# Input_Subsystem.net
KiCad netlist of a schematic drawn in Altium Designer
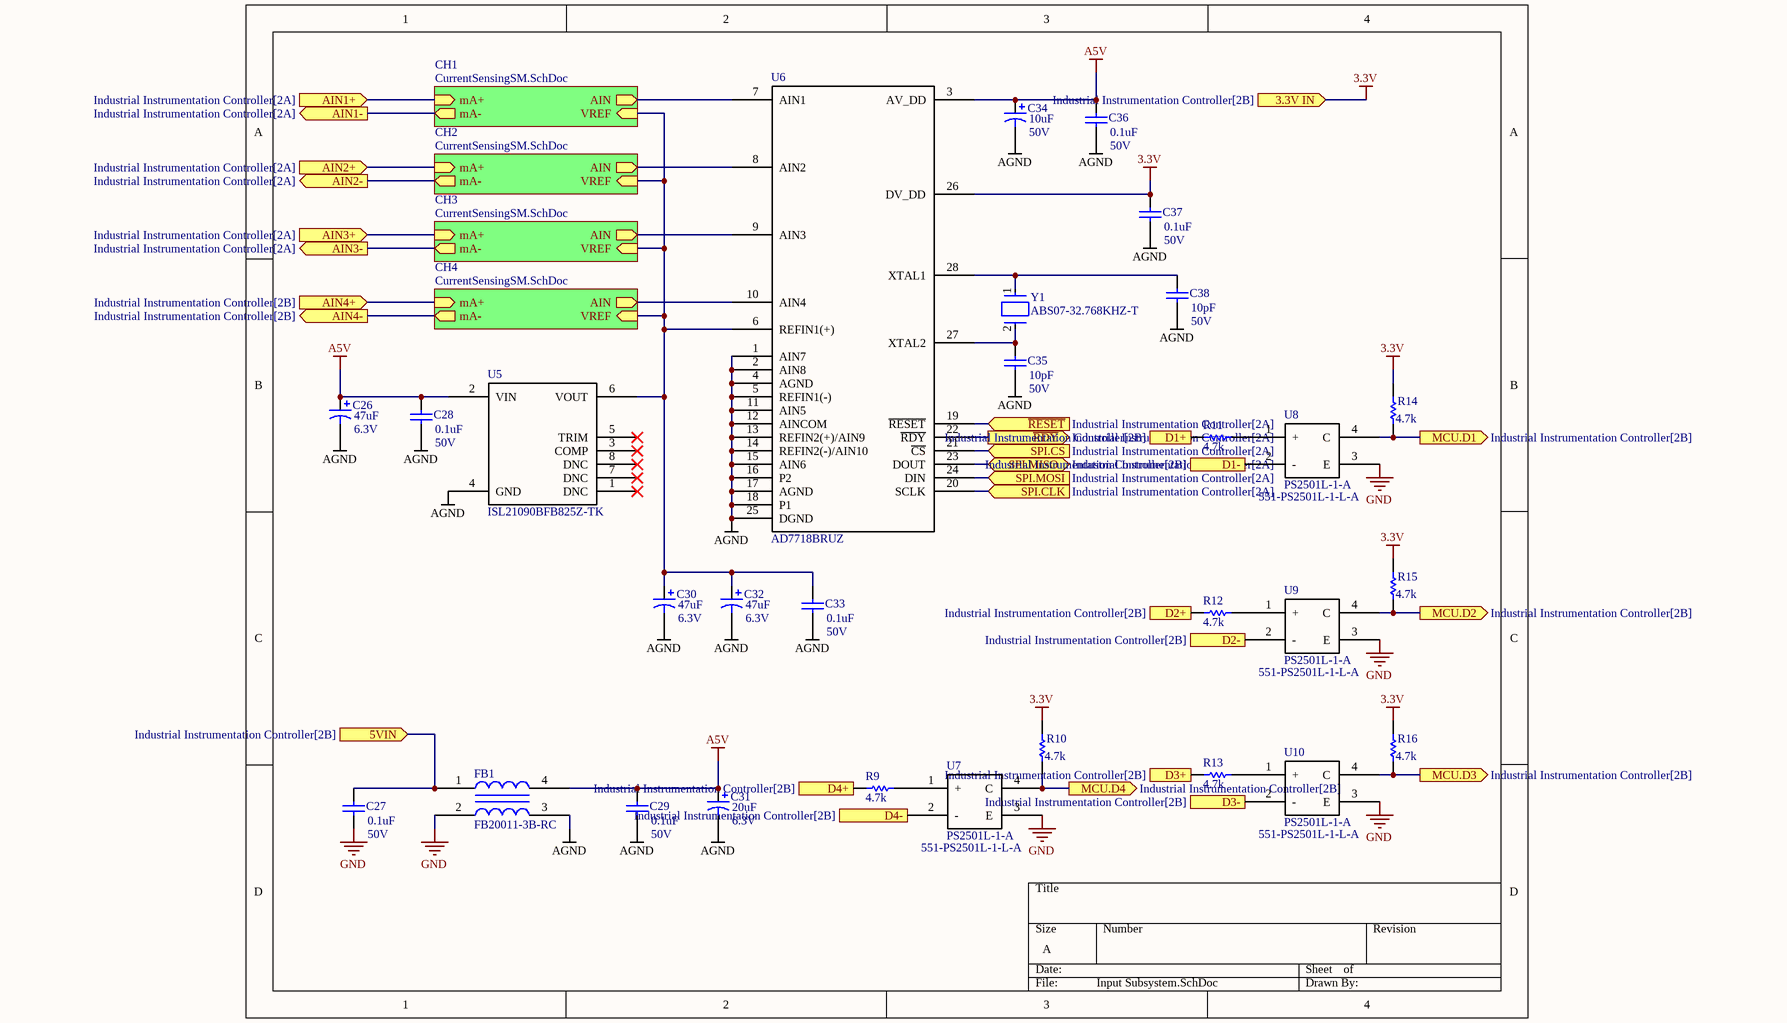
[diagram p0: Input Subsystem.SchDoc]

(export (version "E")
  (design (tool "Eeschema 10.0.6"))
  (components
    (comp (ref "C26")
      (value "47uF")
      (footprint "RB7.6-15")
      (description "Polarized Capacitor (Radial)")
      (fields
        (field (name "VOLTAGE RATING") "6.3V")
        (field (name "Comment") "Cap Pol1")
        (field (name "PUBLISHER") "Altium Limited")
      )
      (libsource (lib "Miscellaneous Devices") (part "Cap Pol1"))
    )
    (comp (ref "C27")
      (value "0.1uF")
      (footprint "RAD-0.3")
      (description "Capacitor")
      (fields
        (field (name "VOLTAGE RATING") "50V")
        (field (name "Comment") "Cap")
        (field (name "PUBLISHER") "Altium Limited")
      )
      (libsource (lib "Miscellaneous Devices") (part "Cap"))
    )
    (comp (ref "C28")
      (value "0.1uF")
      (footprint "RAD-0.3")
      (description "Capacitor")
      (fields
        (field (name "VOLTAGE RATING") "50V")
        (field (name "Comment") "Cap")
        (field (name "PUBLISHER") "Altium Limited")
      )
      (libsource (lib "Miscellaneous Devices") (part "Cap"))
    )
    (comp (ref "C29")
      (value "0.1uF")
      (footprint "RAD-0.3")
      (description "Capacitor")
      (fields
        (field (name "VOLTAGE RATING") "50V")
        (field (name "Comment") "Cap")
        (field (name "PUBLISHER") "Altium Limited")
      )
      (libsource (lib "Miscellaneous Devices") (part "Cap"))
    )
    (comp (ref "C30")
      (value "47uF")
      (footprint "RB7.6-15")
      (description "Polarized Capacitor (Radial)")
      (fields
        (field (name "VOLTAGE RATING") "6.3V")
        (field (name "Comment") "Cap Pol1")
        (field (name "PUBLISHER") "Altium Limited")
      )
      (libsource (lib "Miscellaneous Devices") (part "Cap Pol1"))
    )
    (comp (ref "C31")
      (value "20uF")
      (footprint "RB7.6-15")
      (description "Polarized Capacitor (Radial)")
      (fields
        (field (name "VOLTAGE RATING") "6.3V")
        (field (name "Comment") "Cap Pol1")
        (field (name "PUBLISHER") "Altium Limited")
      )
      (libsource (lib "Miscellaneous Devices") (part "Cap Pol1"))
    )
    (comp (ref "C32")
      (value "47uF")
      (footprint "RB7.6-15")
      (description "Polarized Capacitor (Radial)")
      (fields
        (field (name "VOLTAGE RATING") "6.3V")
        (field (name "Comment") "Cap Pol1")
        (field (name "PUBLISHER") "Altium Limited")
      )
      (libsource (lib "Miscellaneous Devices") (part "Cap Pol1"))
    )
    (comp (ref "C33")
      (value "0.1uF")
      (footprint "RAD-0.3")
      (description "Capacitor")
      (fields
        (field (name "VOLTAGE RATING") "50V")
        (field (name "Comment") "Cap")
        (field (name "PUBLISHER") "Altium Limited")
      )
      (libsource (lib "Miscellaneous Devices") (part "Cap"))
    )
    (comp (ref "C34")
      (value "10uF")
      (footprint "RB7.6-15")
      (description "Polarized Capacitor (Radial)")
      (fields
        (field (name "VOLTAGE RATING") "50V")
        (field (name "Comment") "Cap Pol1")
        (field (name "PUBLISHER") "Altium Limited")
      )
      (libsource (lib "Miscellaneous Devices") (part "Cap Pol1"))
    )
    (comp (ref "C35")
      (value "10pF")
      (footprint "RAD-0.3")
      (description "Capacitor")
      (fields
        (field (name "VOLTAGE RATING") "50V")
        (field (name "Comment") "Cap")
        (field (name "PUBLISHER") "Altium Limited")
      )
      (libsource (lib "Miscellaneous Devices") (part "Cap"))
    )
    (comp (ref "C36")
      (value "0.1uF")
      (footprint "RAD-0.3")
      (description "Capacitor")
      (fields
        (field (name "VOLTAGE RATING") "50V")
        (field (name "Comment") "Cap")
        (field (name "PUBLISHER") "Altium Limited")
      )
      (libsource (lib "Miscellaneous Devices") (part "Cap"))
    )
    (comp (ref "C37")
      (value "0.1uF")
      (footprint "RAD-0.3")
      (description "Capacitor")
      (fields
        (field (name "VOLTAGE RATING") "50V")
        (field (name "Comment") "Cap")
        (field (name "PUBLISHER") "Altium Limited")
      )
      (libsource (lib "Miscellaneous Devices") (part "Cap"))
    )
    (comp (ref "C38")
      (value "10pF")
      (footprint "RAD-0.3")
      (description "Capacitor")
      (fields
        (field (name "VOLTAGE RATING") "50V")
        (field (name "Comment") "Cap")
        (field (name "PUBLISHER") "Altium Limited")
      )
      (libsource (lib "Miscellaneous Devices") (part "Cap"))
    )
    (comp (ref "FB1")
      (value "FB20011-3B-RC")
      (footprint "FB20011")
      (libsource (lib "Parts") (part "FB20011"))
    )
    (comp (ref "R9")
      (value "4.7k")
      (footprint "AXIAL-0.3")
      (description "Resistor")
      (fields (field (name "Comment") "Res1") (field (name "PUBLISHER") "Altium Limited"))
      (libsource (lib "Miscellaneous Devices") (part "Res1"))
    )
    (comp (ref "R10")
      (value "4.7k")
      (footprint "AXIAL-0.3")
      (description "Resistor")
      (fields (field (name "Comment") "Res1") (field (name "PUBLISHER") "Altium Limited"))
      (libsource (lib "Miscellaneous Devices") (part "Res1"))
    )
    (comp (ref "R11")
      (value "4.7k")
      (footprint "AXIAL-0.3")
      (description "Resistor")
      (fields (field (name "Comment") "Res1") (field (name "PUBLISHER") "Altium Limited"))
      (libsource (lib "Miscellaneous Devices") (part "Res1"))
    )
    (comp (ref "R12")
      (value "4.7k")
      (footprint "AXIAL-0.3")
      (description "Resistor")
      (fields (field (name "Comment") "Res1") (field (name "PUBLISHER") "Altium Limited"))
      (libsource (lib "Miscellaneous Devices") (part "Res1"))
    )
    (comp (ref "R13")
      (value "4.7k")
      (footprint "AXIAL-0.3")
      (description "Resistor")
      (fields (field (name "Comment") "Res1") (field (name "PUBLISHER") "Altium Limited"))
      (libsource (lib "Miscellaneous Devices") (part "Res1"))
    )
    (comp (ref "R14")
      (value "4.7k")
      (footprint "AXIAL-0.3")
      (description "Resistor")
      (fields (field (name "Comment") "Res1") (field (name "PUBLISHER") "Altium Limited"))
      (libsource (lib "Miscellaneous Devices") (part "Res1"))
    )
    (comp (ref "R15")
      (value "4.7k")
      (footprint "AXIAL-0.3")
      (description "Resistor")
      (fields (field (name "Comment") "Res1") (field (name "PUBLISHER") "Altium Limited"))
      (libsource (lib "Miscellaneous Devices") (part "Res1"))
    )
    (comp (ref "R16")
      (value "4.7k")
      (footprint "AXIAL-0.3")
      (description "Resistor")
      (fields (field (name "Comment") "Res1") (field (name "PUBLISHER") "Altium Limited"))
      (libsource (lib "Miscellaneous Devices") (part "Res1"))
    )
    (comp (ref "U5")
      (value "ISL21090BFB825Z-TK")
      (footprint "ISL21090BFB825Z-TK")
      (libsource (lib "Parts") (part "ISL21090BFB825Z-TK"))
    )
    (comp (ref "U6")
      (value "AD7718BRUZ")
      (footprint "AD7718BRUZ")
      (libsource (lib "Parts") (part "AD7718BRUZ"))
    )
    (comp (ref "U7")
      (value "PS2501L-1-A")
      (footprint "PS2501L-1-A")
      (description "Optocoupler DC-IN 1-CH Transistor DC-OUT 4-Pin PDIP SMD Magazine")
      (fields
        (field (name "SUPPLIER PART NUMBER 1") "551-PS2501L-1-L-A")
        (field (name "MANUFACTURER") "CEL")
        (field (name "MANUFACTURER PART NUMBER") "PS2501L-1-L-A")
      )
      (libsource (lib "Parts") (part "PS2501L-1-A"))
    )
    (comp (ref "U8")
      (value "PS2501L-1-A")
      (footprint "PS2501L-1-A")
      (description "Optocoupler DC-IN 1-CH Transistor DC-OUT 4-Pin PDIP SMD Magazine")
      (fields
        (field (name "SUPPLIER PART NUMBER 1") "551-PS2501L-1-L-A")
        (field (name "MANUFACTURER") "CEL")
        (field (name "MANUFACTURER PART NUMBER") "PS2501L-1-L-A")
      )
      (libsource (lib "Parts") (part "PS2501L-1-A"))
    )
    (comp (ref "U9")
      (value "PS2501L-1-A")
      (footprint "PS2501L-1-A")
      (description "Optocoupler DC-IN 1-CH Transistor DC-OUT 4-Pin PDIP SMD Magazine")
      (fields
        (field (name "SUPPLIER PART NUMBER 1") "551-PS2501L-1-L-A")
        (field (name "MANUFACTURER") "CEL")
        (field (name "MANUFACTURER PART NUMBER") "PS2501L-1-L-A")
      )
      (libsource (lib "Parts") (part "PS2501L-1-A"))
    )
    (comp (ref "U10")
      (value "PS2501L-1-A")
      (footprint "PS2501L-1-A")
      (description "Optocoupler DC-IN 1-CH Transistor DC-OUT 4-Pin PDIP SMD Magazine")
      (fields
        (field (name "SUPPLIER PART NUMBER 1") "551-PS2501L-1-L-A")
        (field (name "MANUFACTURER") "CEL")
        (field (name "MANUFACTURER PART NUMBER") "PS2501L-1-L-A")
      )
      (libsource (lib "Parts") (part "PS2501L-1-A"))
    )
    (comp (ref "Y1")
      (value "ABS07-32.768KHZ-T")
      (footprint "FP-ABS07-MFG")
      (description "Crystal 32.768kHz ±20ppm (Tol) 12.5pF FUND 70kΩ 2-Pin CSMD T/R")
      (fields (field (name "TOLERANCE") "20ppm"))
      (libsource (lib "Altium Content Vault") (part "c23a69dc6c9e2f18f2079038eb95dd1"))
    )
  )
  (nets
    (net (code "1") (name "/5VIN") (class "Default")
      (node (ref "C27") (pin "2") (pinfunction "2_2") (pintype "passive"))
      (node (ref "FB1") (pin "1") (pinfunction "5V_1") (pintype "passive"))
    )
    (net (code "2") (name "/AIN") (class "Default")
      (node (ref "U6") (pin "9") (pinfunction "AIN3_9") (pintype "passive"))
    )
    (net (code "11") (name "/AIN_1") (class "Default")
      (node (ref "U6") (pin "10") (pinfunction "AIN4_10") (pintype "passive"))
    )
    (net (code "12") (name "/AIN_2") (class "Default")
      (node (ref "U6") (pin "7") (pinfunction "AIN1_7") (pintype "passive"))
    )
    (net (code "13") (name "/AIN_3") (class "Default")
      (node (ref "U6") (pin "8") (pinfunction "AIN2_8") (pintype "passive"))
    )
    (net (code "14") (name "/D1+") (class "Default")
      (node (ref "R11") (pin "2") (pinfunction "2_2") (pintype "passive"))
    )
    (net (code "15") (name "/D1-") (class "Default")
      (node (ref "U8") (pin "2") (pinfunction "-_2") (pintype "passive"))
    )
    (net (code "16") (name "/D2+") (class "Default")
      (node (ref "R12") (pin "2") (pinfunction "2_2") (pintype "passive"))
    )
    (net (code "17") (name "/D2-") (class "Default")
      (node (ref "U9") (pin "2") (pinfunction "-_2") (pintype "passive"))
    )
    (net (code "18") (name "/D3+") (class "Default")
      (node (ref "R13") (pin "2") (pinfunction "2_2") (pintype "passive"))
    )
    (net (code "19") (name "/D3-") (class "Default")
      (node (ref "U10") (pin "2") (pinfunction "-_2") (pintype "passive"))
    )
    (net (code "20") (name "/D4+") (class "Default")
      (node (ref "R9") (pin "2") (pinfunction "2_2") (pintype "passive"))
    )
    (net (code "21") (name "/D4-") (class "Default")
      (node (ref "U7") (pin "2") (pinfunction "-_2") (pintype "passive"))
    )
    (net (code "22") (name "/MCU.D1") (class "Default")
      (node (ref "R14") (pin "1") (pinfunction "1_1") (pintype "passive"))
      (node (ref "U8") (pin "4") (pinfunction "C_4") (pintype "passive"))
    )
    (net (code "23") (name "/MCU.D2") (class "Default")
      (node (ref "R15") (pin "1") (pinfunction "1_1") (pintype "passive"))
      (node (ref "U9") (pin "4") (pinfunction "C_4") (pintype "passive"))
    )
    (net (code "24") (name "/MCU.D3") (class "Default")
      (node (ref "R16") (pin "1") (pinfunction "1_1") (pintype "passive"))
      (node (ref "U10") (pin "4") (pinfunction "C_4") (pintype "passive"))
    )
    (net (code "25") (name "/MCU.D4") (class "Default")
      (node (ref "R10") (pin "1") (pinfunction "1_1") (pintype "passive"))
      (node (ref "U7") (pin "4") (pinfunction "C_4") (pintype "passive"))
    )
    (net (code "26") (name "/SPI.CLK") (class "Default")
      (node (ref "U6") (pin "20") (pinfunction "SCLK_20") (pintype "passive"))
    )
    (net (code "27") (name "/SPI.CS") (class "Default")
      (node (ref "U6") (pin "21") (pinfunction "~{CS}_21") (pintype "passive"))
    )
    (net (code "28") (name "/SPI.MISO") (class "Default")
      (node (ref "U6") (pin "23") (pinfunction "DOUT_23") (pintype "passive"))
    )
    (net (code "29") (name "/SPI.MOSI") (class "Default")
      (node (ref "U6") (pin "24") (pinfunction "DIN_24") (pintype "passive"))
    )
    (net (code "30") (name "/VREF") (class "Default")
      (node (ref "C30") (pin "1") (pinfunction "1_1") (pintype "passive"))
      (node (ref "C32") (pin "1") (pinfunction "1_1") (pintype "passive"))
      (node (ref "C33") (pin "2") (pinfunction "2_2") (pintype "passive"))
      (node (ref "U5") (pin "6") (pinfunction "VOUT_6") (pintype "passive"))
      (node (ref "U6") (pin "6") (pinfunction "REFIN1(+)_6") (pintype "passive"))
    )
    (net (code "31") (name "/~{RDY}") (class "Default")
      (node (ref "U6") (pin "22") (pinfunction "~{RDY}_22") (pintype "passive"))
    )
    (net (code "32") (name "/~{RESET}") (class "Default")
      (node (ref "U6") (pin "19") (pinfunction "~{RESET}_19") (pintype "passive"))
    )
    (net (code "33") (name "3.3V") (class "Default")
      (node (ref "C37") (pin "2") (pinfunction "2_2") (pintype "passive"))
      (node (ref "R10") (pin "2") (pinfunction "2_2") (pintype "passive"))
      (node (ref "R14") (pin "2") (pinfunction "2_2") (pintype "passive"))
      (node (ref "R15") (pin "2") (pinfunction "2_2") (pintype "passive"))
      (node (ref "R16") (pin "2") (pinfunction "2_2") (pintype "passive"))
      (node (ref "U6") (pin "26") (pinfunction "DV_DD_26") (pintype "passive"))
    )
    (net (code "34") (name "A5V") (class "Default")
      (node (ref "C26") (pin "1") (pinfunction "1_1") (pintype "passive"))
      (node (ref "C28") (pin "2") (pinfunction "2_2") (pintype "passive"))
      (node (ref "C29") (pin "2") (pinfunction "2_2") (pintype "passive"))
      (node (ref "C31") (pin "1") (pinfunction "1_1") (pintype "passive"))
      (node (ref "C34") (pin "1") (pinfunction "1_1") (pintype "passive"))
      (node (ref "C36") (pin "2") (pinfunction "2_2") (pintype "passive"))
      (node (ref "FB1") (pin "4") (pinfunction "A5V_4") (pintype "passive"))
      (node (ref "U5") (pin "2") (pinfunction "VIN_2") (pintype "passive"))
      (node (ref "U6") (pin "3") (pinfunction "AV_DD_3") (pintype "passive"))
    )
    (net (code "35") (name "AGND") (class "Default")
      (node (ref "C26") (pin "2") (pinfunction "2_2") (pintype "passive"))
      (node (ref "C28") (pin "1") (pinfunction "1_1") (pintype "passive"))
      (node (ref "C29") (pin "1") (pinfunction "1_1") (pintype "passive"))
      (node (ref "C30") (pin "2") (pinfunction "2_2") (pintype "passive"))
      (node (ref "C31") (pin "2") (pinfunction "2_2") (pintype "passive"))
      (node (ref "C32") (pin "2") (pinfunction "2_2") (pintype "passive"))
      (node (ref "C33") (pin "1") (pinfunction "1_1") (pintype "passive"))
      (node (ref "C34") (pin "2") (pinfunction "2_2") (pintype "passive"))
      (node (ref "C35") (pin "1") (pinfunction "1_1") (pintype "passive"))
      (node (ref "C36") (pin "1") (pinfunction "1_1") (pintype "passive"))
      (node (ref "C37") (pin "1") (pinfunction "1_1") (pintype "passive"))
      (node (ref "C38") (pin "1") (pinfunction "1_1") (pintype "passive"))
      (node (ref "FB1") (pin "3") (pinfunction "AGND_3") (pintype "passive"))
      (node (ref "U5") (pin "4") (pinfunction "GND_4") (pintype "passive"))
      (node (ref "U6") (pin "1") (pinfunction "AIN7_1") (pintype "passive"))
      (node (ref "U6") (pin "11") (pinfunction "AIN5_11") (pintype "passive"))
      (node (ref "U6") (pin "12") (pinfunction "AINCOM_12") (pintype "passive"))
      (node (ref "U6") (pin "13") (pinfunction "REFIN2(+)/AIN9_13") (pintype "passive"))
      (node (ref "U6") (pin "14") (pinfunction "REFIN2(-)/AIN10_14") (pintype "passive"))
      (node (ref "U6") (pin "15") (pinfunction "AIN6_15") (pintype "passive"))
      (node (ref "U6") (pin "16") (pinfunction "P2_16") (pintype "passive"))
      (node (ref "U6") (pin "17") (pinfunction "AGND_17") (pintype "passive"))
      (node (ref "U6") (pin "18") (pinfunction "P1_18") (pintype "passive"))
      (node (ref "U6") (pin "2") (pinfunction "AIN8_2") (pintype "passive"))
      (node (ref "U6") (pin "25") (pinfunction "DGND_25") (pintype "passive"))
      (node (ref "U6") (pin "4") (pinfunction "AGND_4") (pintype "passive"))
      (node (ref "U6") (pin "5") (pinfunction "REFIN1(-)_5") (pintype "passive"))
    )
    (net (code "36") (name "GND") (class "Default")
      (node (ref "C27") (pin "1") (pinfunction "1_1") (pintype "passive"))
      (node (ref "FB1") (pin "2") (pinfunction "GND_2") (pintype "passive"))
      (node (ref "U10") (pin "3") (pinfunction "E_3") (pintype "passive"))
      (node (ref "U7") (pin "3") (pinfunction "E_3") (pintype "passive"))
      (node (ref "U8") (pin "3") (pinfunction "E_3") (pintype "passive"))
      (node (ref "U9") (pin "3") (pinfunction "E_3") (pintype "passive"))
    )
    (net (code "37") (name "Net-(U6-XTAL1)") (class "Default")
      (node (ref "C38") (pin "2") (pinfunction "2_2") (pintype "passive"))
      (node (ref "U6") (pin "28") (pinfunction "XTAL1_28") (pintype "passive"))
      (node (ref "Y1") (pin "1") (pinfunction "1_1") (pintype "passive"))
    )
    (net (code "38") (name "Net-(U6-XTAL2)") (class "Default")
      (node (ref "C35") (pin "2") (pinfunction "2_2") (pintype "passive"))
      (node (ref "U6") (pin "27") (pinfunction "XTAL2_27") (pintype "passive"))
      (node (ref "Y1") (pin "2") (pinfunction "2_2") (pintype "passive"))
    )
    (net (code "39") (name "Net-(U7-+)") (class "Default")
      (node (ref "R9") (pin "1") (pinfunction "1_1") (pintype "passive"))
      (node (ref "U7") (pin "1") (pinfunction "+_1") (pintype "passive"))
    )
    (net (code "40") (name "Net-(U8-+)") (class "Default")
      (node (ref "R11") (pin "1") (pinfunction "1_1") (pintype "passive"))
      (node (ref "U8") (pin "1") (pinfunction "+_1") (pintype "passive"))
    )
    (net (code "41") (name "Net-(U9-+)") (class "Default")
      (node (ref "R12") (pin "1") (pinfunction "1_1") (pintype "passive"))
      (node (ref "U9") (pin "1") (pinfunction "+_1") (pintype "passive"))
    )
    (net (code "42") (name "Net-(U10-+)") (class "Default")
      (node (ref "R13") (pin "1") (pinfunction "1_1") (pintype "passive"))
      (node (ref "U10") (pin "1") (pinfunction "+_1") (pintype "passive"))
    )
    (net (code "43") (name "unconnected-(U5-COMP-Pad3)") (class "Default")
      (node (ref "U5") (pin "3") (pinfunction "COMP_3") (pintype "passive+no_connect"))
    )
    (net (code "44") (name "unconnected-(U5-DNC-Pad1)") (class "Default")
      (node (ref "U5") (pin "1") (pinfunction "DNC_1") (pintype "passive+no_connect"))
    )
    (net (code "45") (name "unconnected-(U5-DNC-Pad7)") (class "Default")
      (node (ref "U5") (pin "7") (pinfunction "DNC_7") (pintype "passive+no_connect"))
    )
    (net (code "46") (name "unconnected-(U5-DNC-Pad8)") (class "Default")
      (node (ref "U5") (pin "8") (pinfunction "DNC_8") (pintype "passive+no_connect"))
    )
    (net (code "47") (name "unconnected-(U5-TRIM-Pad5)") (class "Default")
      (node (ref "U5") (pin "5") (pinfunction "TRIM_5") (pintype "passive+no_connect"))
    )
  )
)
